# SCH_Finger_CLeaner_IC_Controller_2025-11.net
KiCad netlist of a schematic drawn in EasyEDA
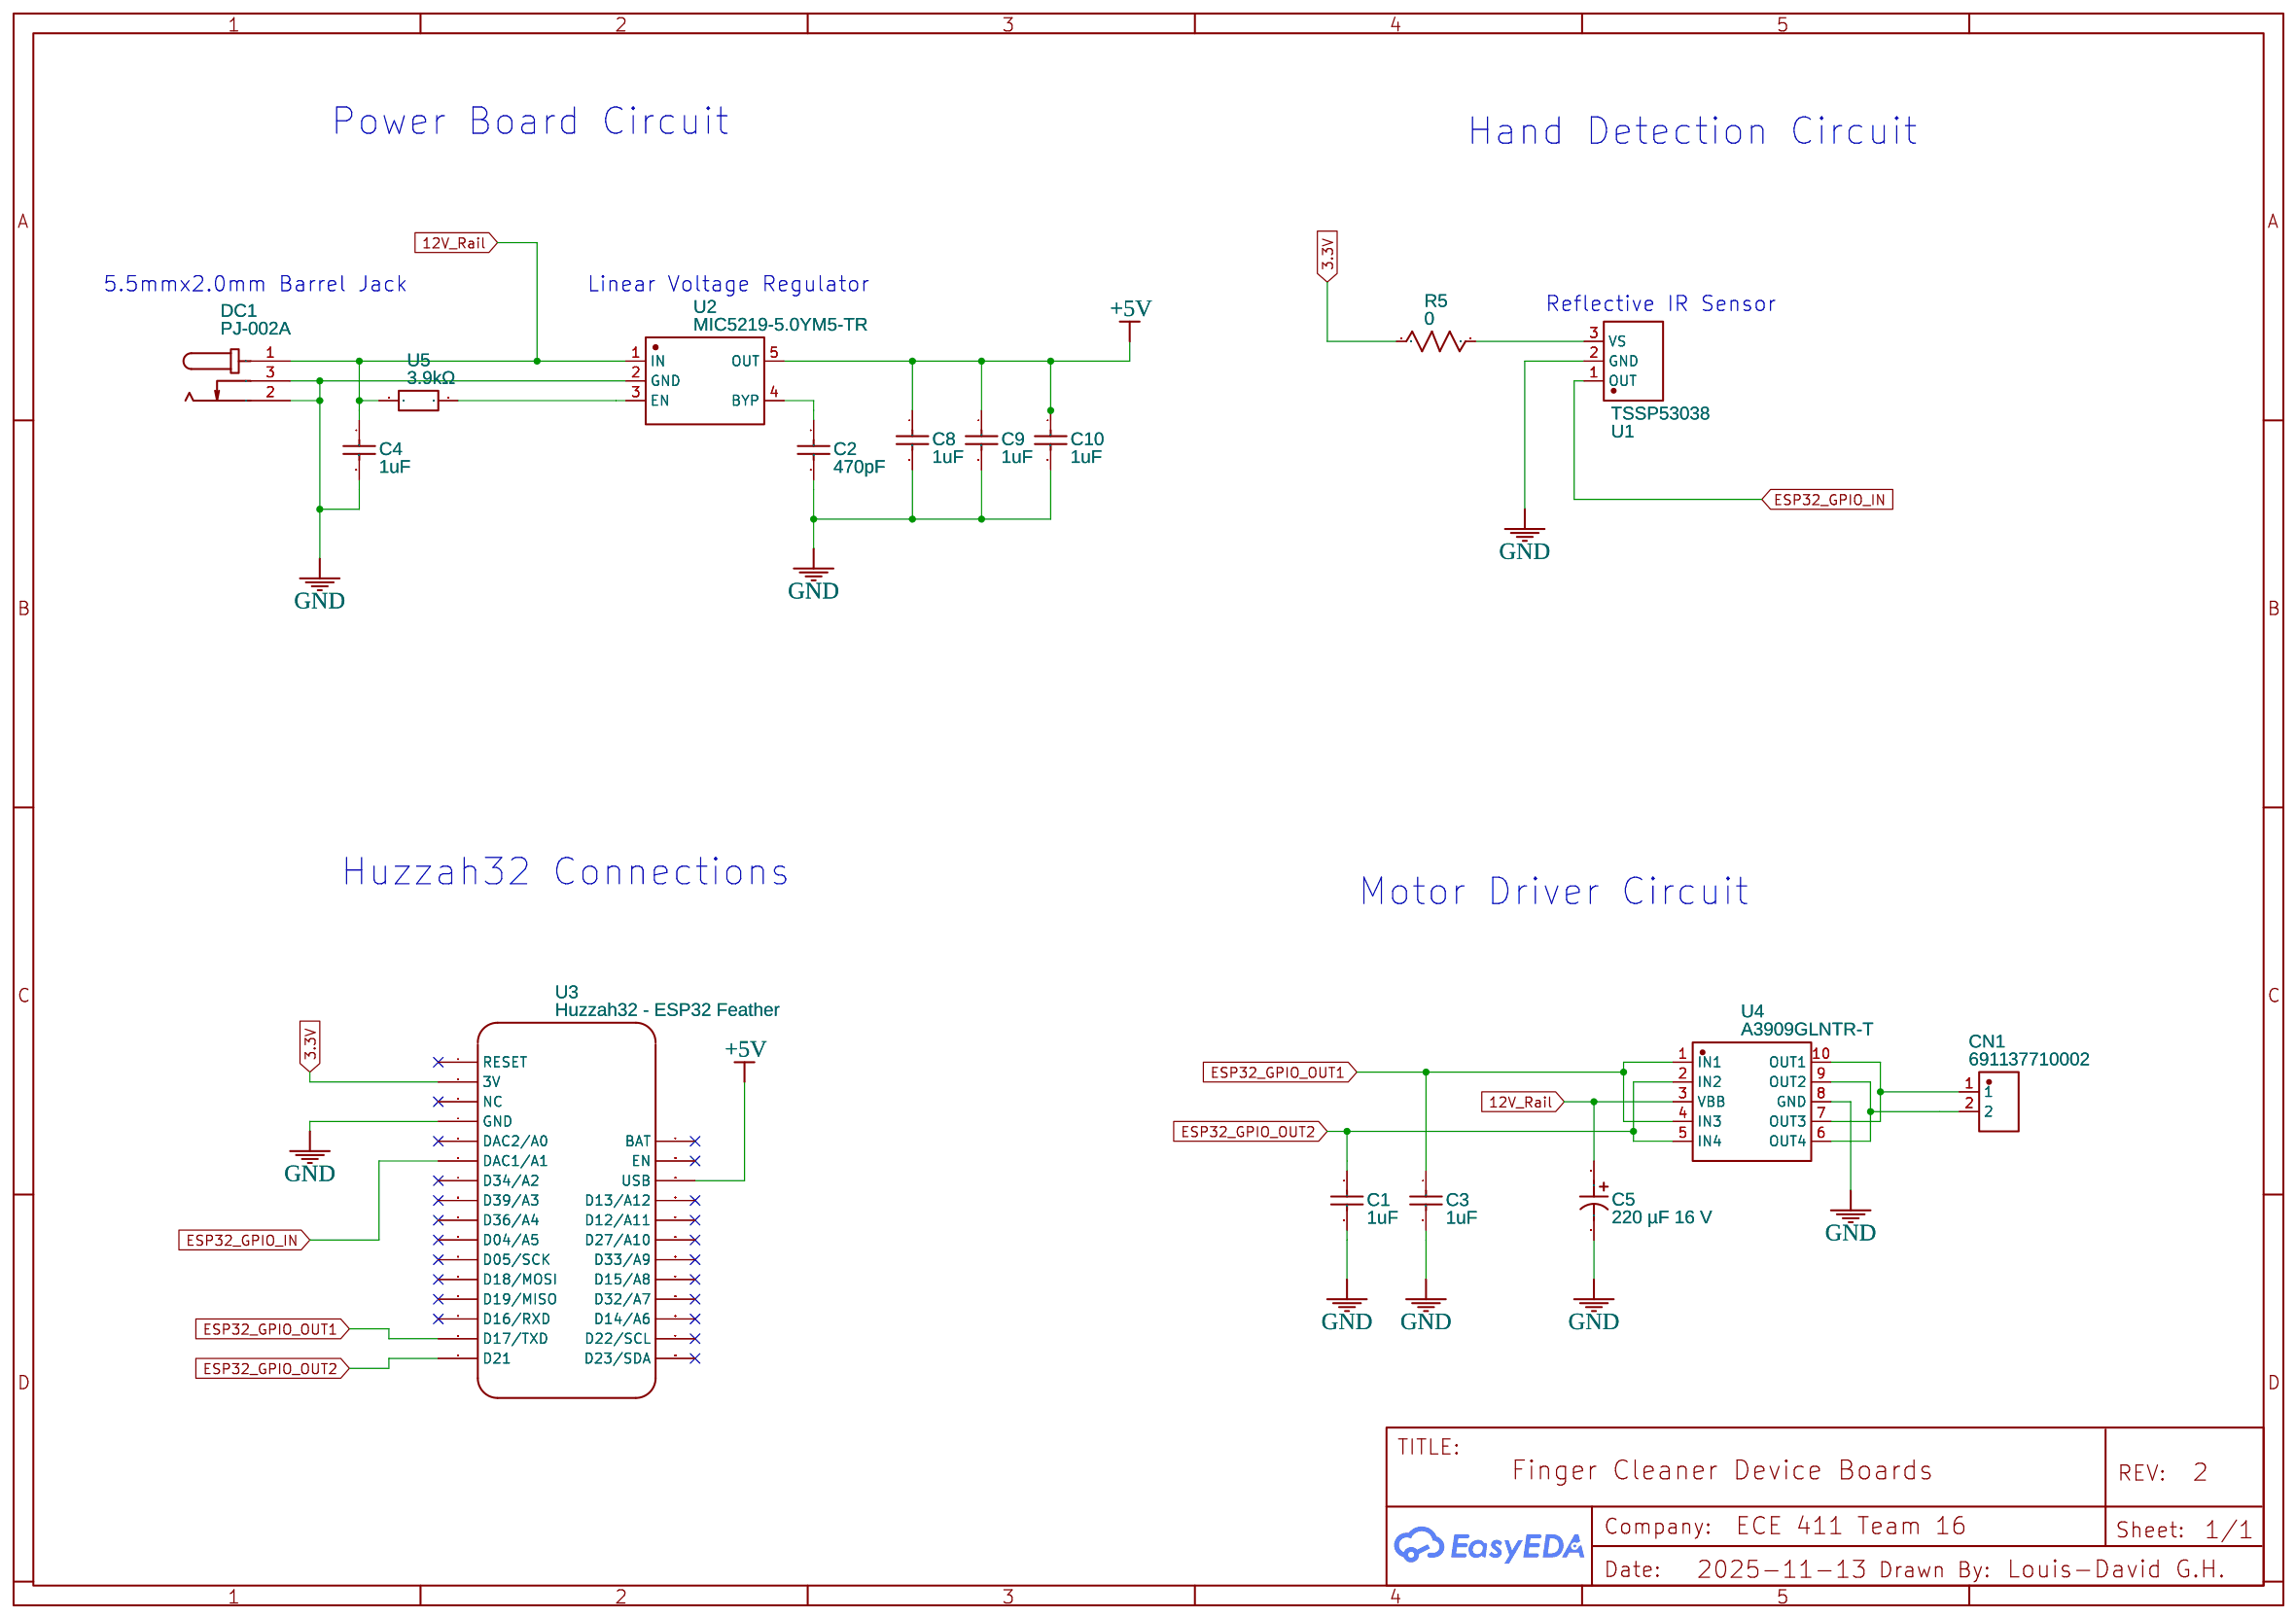
[diagram p0: schematic sheet]

(export (version "E")
  (design (tool "Eeschema 10.0.6"))
  (components
    (comp (ref "C1")
      (value "1uF")
      (fields
        (field (name "Manufacturer Part") "CL10B105KO8NNNC")
        (field (name "Manufacturer") "SAMSUNG(三星)")
      )
      (libsource (lib "") (part "CL10B105KO8NNNC"))
    )
    (comp (ref "C2")
      (value "470pF")
      (fields
        (field (name "Manufacturer Part") "CL10C471JB8NNNC")
        (field (name "Manufacturer") "SAMSUNG(三星)")
      )
      (libsource (lib "") (part "CL10C471JB8NNNC"))
    )
    (comp (ref "C3")
      (value "1uF")
      (fields
        (field (name "Manufacturer Part") "CL10B105KO8NNNC")
        (field (name "Manufacturer") "SAMSUNG(三星)")
      )
      (libsource (lib "") (part "CL10B105KO8NNNC"))
    )
    (comp (ref "C4")
      (value "1uF")
      (fields
        (field (name "Manufacturer Part") "CL10B105KO8NNNC")
        (field (name "Manufacturer") "SAMSUNG(三星)")
      )
      (libsource (lib "") (part "CL10B105KO8NNNC"))
    )
    (comp (ref "C5")
      (value "220 µF 16 V")
      (fields
        (field (name "Manufacturer Part") "APXG160ARA221MF80G")
        (field (name "Manufacturer") "Chemi-Con")
      )
      (libsource (lib "") (part "APXG160ARA221MF80G - 220 µF 16 V"))
    )
    (comp (ref "C8")
      (value "1uF")
      (fields
        (field (name "Manufacturer Part") "CL10B105KO8NNNC")
        (field (name "Manufacturer") "SAMSUNG(三星)")
      )
      (libsource (lib "") (part "CL10B105KO8NNNC"))
    )
    (comp (ref "C9")
      (value "1uF")
      (fields
        (field (name "Manufacturer Part") "CL10B105KO8NNNC")
        (field (name "Manufacturer") "SAMSUNG(三星)")
      )
      (libsource (lib "") (part "CL10B105KO8NNNC"))
    )
    (comp (ref "C10")
      (value "1uF")
      (fields
        (field (name "Manufacturer Part") "CL10B105KO8NNNC")
        (field (name "Manufacturer") "SAMSUNG(三星)")
      )
      (libsource (lib "") (part "CL10B105KO8NNNC"))
    )
    (comp (ref "CN1")
      (value "691137710002")
      (fields (field (name "Manufacturer") "Wurth(伍尔特)"))
      (libsource (lib "") (part "691137710002"))
    )
    (comp (ref "DC1")
      (value "PJ-002A")
      (fields (field (name "Manufacturer") "CUI"))
      (libsource (lib "") (part "PJ-002A"))
    )
    (comp (ref "R5") (value "0") (libsource (lib "") (part "R_0603_US")))
    (comp (ref "U1")
      (value "TSSP53038")
      (fields (field (name "Manufacturer") "VISHAY(威世)"))
      (libsource (lib "") (part "TSSP53038"))
    )
    (comp (ref "U2")
      (value "MIC5219-5.0YM5-TR")
      (fields (field (name "Manufacturer") "MICROCHIP(美国微芯)"))
      (libsource (lib "") (part "MIC5219-5.0YM5-TR"))
    )
    (comp (ref "U3")
      (value "Huzzah32 - ESP32 Feather")
      (fields (field (name "Manufacturer Part") "3405") (field (name "Manufacturer") "Adafruit"))
      (libsource (lib "") (part "Huzzah32 - ESP32 Feather"))
    )
    (comp (ref "U4")
      (value "A3909GLNTR-T")
      (fields (field (name "Manufacturer") "ALLEGRO(美国埃戈罗)"))
      (libsource (lib "") (part "A3909GLNTR-T"))
    )
    (comp (ref "U5")
      (value "3.9kΩ")
      (fields
        (field (name "Manufacturer Part") "CRCW08053K90FKEAC")
        (field (name "Manufacturer") "VISHAY(威世)")
      )
      (libsource (lib "") (part "CRCW08053K90FKEAC"))
    )
  )
  (nets
    (net (code "1") (name "+5V") (class "Default")
      (node (ref "C10") (pin "1") (pinfunction "1_1") (pintype "input"))
      (node (ref "C8") (pin "1") (pinfunction "1_1") (pintype "input"))
      (node (ref "C9") (pin "1") (pinfunction "1_1") (pintype "input"))
      (node (ref "U2") (pin "5") (pinfunction "OUT_5") (pintype "unspecified"))
      (node (ref "U3") (pin "19") (pinfunction "USB_19") (pintype "unspecified"))
    )
    (net (code "2") (name "3.3V") (class "Default")
      (node (ref "R5") (pin "1") (pinfunction "1_1") (pintype "unspecified"))
      (node (ref "U3") (pin "2") (pinfunction "3V_2") (pintype "unspecified"))
    )
    (net (code "3") (name "12V_Rail") (class "Default")
      (node (ref "C4") (pin "1") (pinfunction "1_1") (pintype "input"))
      (node (ref "C5") (pin "1") (pinfunction "1_1") (pintype "input"))
      (node (ref "DC1") (pin "1") (pinfunction "1_1") (pintype "unspecified"))
      (node (ref "U2") (pin "1") (pinfunction "IN_1") (pintype "unspecified"))
      (node (ref "U4") (pin "3") (pinfunction "VBB_3") (pintype "unspecified"))
      (node (ref "U5") (pin "1") (pinfunction "1_1") (pintype "unspecified"))
    )
    (net (code "4") (name "ESP32_GPIO_IN") (class "Default")
      (node (ref "U1") (pin "1") (pinfunction "OUT_1") (pintype "unspecified"))
      (node (ref "U3") (pin "6") (pinfunction "DAC1/A1_6") (pintype "unspecified"))
    )
    (net (code "5") (name "ESP32_GPIO_OUT1") (class "Default")
      (node (ref "C3") (pin "1") (pinfunction "1_1") (pintype "input"))
      (node (ref "U3") (pin "15") (pinfunction "D17/TXD_15") (pintype "unspecified"))
      (node (ref "U4") (pin "1") (pinfunction "IN1_1") (pintype "unspecified"))
      (node (ref "U4") (pin "4") (pinfunction "IN3_4") (pintype "unspecified"))
    )
    (net (code "6") (name "ESP32_GPIO_OUT2") (class "Default")
      (node (ref "C1") (pin "1") (pinfunction "1_1") (pintype "input"))
      (node (ref "U3") (pin "16") (pinfunction "D21_16") (pintype "unspecified"))
      (node (ref "U4") (pin "2") (pinfunction "IN2_2") (pintype "unspecified"))
      (node (ref "U4") (pin "5") (pinfunction "IN4_5") (pintype "unspecified"))
    )
    (net (code "7") (name "GND") (class "Default")
      (node (ref "C1") (pin "2") (pinfunction "2_2") (pintype "input"))
      (node (ref "C10") (pin "2") (pinfunction "2_2") (pintype "input"))
      (node (ref "C2") (pin "2") (pinfunction "2_2") (pintype "input"))
      (node (ref "C3") (pin "2") (pinfunction "2_2") (pintype "input"))
      (node (ref "C4") (pin "2") (pinfunction "2_2") (pintype "input"))
      (node (ref "C5") (pin "2") (pinfunction "2_2") (pintype "input"))
      (node (ref "C8") (pin "2") (pinfunction "2_2") (pintype "input"))
      (node (ref "C9") (pin "2") (pinfunction "2_2") (pintype "input"))
      (node (ref "DC1") (pin "2") (pinfunction "2_2") (pintype "unspecified"))
      (node (ref "DC1") (pin "3") (pinfunction "3_3") (pintype "unspecified"))
      (node (ref "U1") (pin "2") (pinfunction "GND_2") (pintype "unspecified"))
      (node (ref "U2") (pin "2") (pinfunction "GND_2") (pintype "unspecified"))
      (node (ref "U3") (pin "4") (pinfunction "GND_4") (pintype "unspecified"))
      (node (ref "U4") (pin "8") (pinfunction "GND_8") (pintype "unspecified"))
    )
    (net (code "8") (name "Net-(U1-VS)") (class "Default")
      (node (ref "R5") (pin "2") (pinfunction "2_2") (pintype "unspecified"))
      (node (ref "U1") (pin "3") (pinfunction "VS_3") (pintype "unspecified"))
    )
    (net (code "9") (name "Net-(U2-BYP)") (class "Default")
      (node (ref "C2") (pin "1") (pinfunction "1_1") (pintype "input"))
      (node (ref "U2") (pin "4") (pinfunction "BYP_4") (pintype "unspecified"))
    )
    (net (code "10") (name "Net-(U2-EN)") (class "Default")
      (node (ref "U2") (pin "3") (pinfunction "EN_3") (pintype "unspecified"))
      (node (ref "U5") (pin "2") (pinfunction "2_2") (pintype "unspecified"))
    )
    (net (code "11") (name "Net-(U4-OUT1)") (class "Default")
      (node (ref "CN1") (pin "1") (pinfunction "1_1") (pintype "unspecified"))
      (node (ref "U4") (pin "10") (pinfunction "OUT1_10") (pintype "unspecified"))
      (node (ref "U4") (pin "7") (pinfunction "OUT3_7") (pintype "unspecified"))
    )
    (net (code "12") (name "Net-(U4-OUT2)") (class "Default")
      (node (ref "CN1") (pin "2") (pinfunction "2_2") (pintype "unspecified"))
      (node (ref "U4") (pin "6") (pinfunction "OUT4_6") (pintype "unspecified"))
      (node (ref "U4") (pin "9") (pinfunction "OUT2_9") (pintype "unspecified"))
    )
    (net (code "13") (name "unconnected-(U3-BAT-Pad17)") (class "Default")
      (node (ref "U3") (pin "17") (pinfunction "BAT_17") (pintype "unspecified+no_connect"))
    )
    (net (code "14") (name "unconnected-(U3-D04{slash}A5-Pad10)") (class "Default")
      (node (ref "U3") (pin "10") (pinfunction "D04/A5_10") (pintype "unspecified+no_connect"))
    )
    (net (code "15") (name "unconnected-(U3-D05{slash}SCK-Pad11)") (class "Default")
      (node (ref "U3") (pin "11") (pinfunction "D05/SCK_11") (pintype "unspecified+no_connect"))
    )
    (net (code "16") (name "unconnected-(U3-D12{slash}A11-Pad21)") (class "Default")
      (node (ref "U3") (pin "21") (pinfunction "D12/A11_21") (pintype "unspecified+no_connect"))
    )
    (net (code "17") (name "unconnected-(U3-D13{slash}A12-Pad20)") (class "Default")
      (node (ref "U3") (pin "20") (pinfunction "D13/A12_20") (pintype "unspecified+no_connect"))
    )
    (net (code "18") (name "unconnected-(U3-D14{slash}A6-Pad26)") (class "Default")
      (node (ref "U3") (pin "26") (pinfunction "D14/A6_26") (pintype "unspecified+no_connect"))
    )
    (net (code "19") (name "unconnected-(U3-D15{slash}A8-Pad24)") (class "Default")
      (node (ref "U3") (pin "24") (pinfunction "D15/A8_24") (pintype "unspecified+no_connect"))
    )
    (net (code "20") (name "unconnected-(U3-D16{slash}RXD-Pad14)") (class "Default")
      (node (ref "U3") (pin "14") (pinfunction "D16/RXD_14") (pintype "unspecified+no_connect"))
    )
    (net (code "21") (name "unconnected-(U3-D18{slash}MOSI-Pad12)") (class "Default")
      (node (ref "U3") (pin "12") (pinfunction "D18/MOSI_12") (pintype "unspecified+no_connect"))
    )
    (net (code "22") (name "unconnected-(U3-D19{slash}MISO-Pad13)") (class "Default")
      (node (ref "U3") (pin "13") (pinfunction "D19/MISO_13") (pintype "unspecified+no_connect"))
    )
    (net (code "23") (name "unconnected-(U3-D22{slash}SCL-Pad27)") (class "Default")
      (node (ref "U3") (pin "27") (pinfunction "D22/SCL_27") (pintype "unspecified+no_connect"))
    )
    (net (code "24") (name "unconnected-(U3-D23{slash}SDA-Pad28)") (class "Default")
      (node (ref "U3") (pin "28") (pinfunction "D23/SDA_28") (pintype "unspecified+no_connect"))
    )
    (net (code "25") (name "unconnected-(U3-D27{slash}A10-Pad22)") (class "Default")
      (node (ref "U3") (pin "22") (pinfunction "D27/A10_22") (pintype "unspecified+no_connect"))
    )
    (net (code "26") (name "unconnected-(U3-D32{slash}A7-Pad25)") (class "Default")
      (node (ref "U3") (pin "25") (pinfunction "D32/A7_25") (pintype "unspecified+no_connect"))
    )
    (net (code "27") (name "unconnected-(U3-D33{slash}A9-Pad23)") (class "Default")
      (node (ref "U3") (pin "23") (pinfunction "D33/A9_23") (pintype "unspecified+no_connect"))
    )
    (net (code "28") (name "unconnected-(U3-D34{slash}A2-Pad7)") (class "Default")
      (node (ref "U3") (pin "7") (pinfunction "D34/A2_7") (pintype "unspecified+no_connect"))
    )
    (net (code "29") (name "unconnected-(U3-D36{slash}A4-Pad9)") (class "Default")
      (node (ref "U3") (pin "9") (pinfunction "D36/A4_9") (pintype "unspecified+no_connect"))
    )
    (net (code "30") (name "unconnected-(U3-D39{slash}A3-Pad8)") (class "Default")
      (node (ref "U3") (pin "8") (pinfunction "D39/A3_8") (pintype "unspecified+no_connect"))
    )
    (net (code "31") (name "unconnected-(U3-DAC2{slash}A0-Pad5)") (class "Default")
      (node (ref "U3") (pin "5") (pinfunction "DAC2/A0_5") (pintype "unspecified+no_connect"))
    )
    (net (code "32") (name "unconnected-(U3-EN-Pad18)") (class "Default")
      (node (ref "U3") (pin "18") (pinfunction "EN_18") (pintype "unspecified+no_connect"))
    )
    (net (code "33") (name "unconnected-(U3-NC-Pad3)") (class "Default")
      (node (ref "U3") (pin "3") (pinfunction "NC_3") (pintype "unspecified+no_connect"))
    )
    (net (code "34") (name "unconnected-(U3-RESET-Pad1)") (class "Default")
      (node (ref "U3") (pin "1") (pinfunction "RESET_1") (pintype "unspecified+no_connect"))
    )
  )
)
